# BSPD.net
KiCad netlist of a schematic drawn in Altium Designer
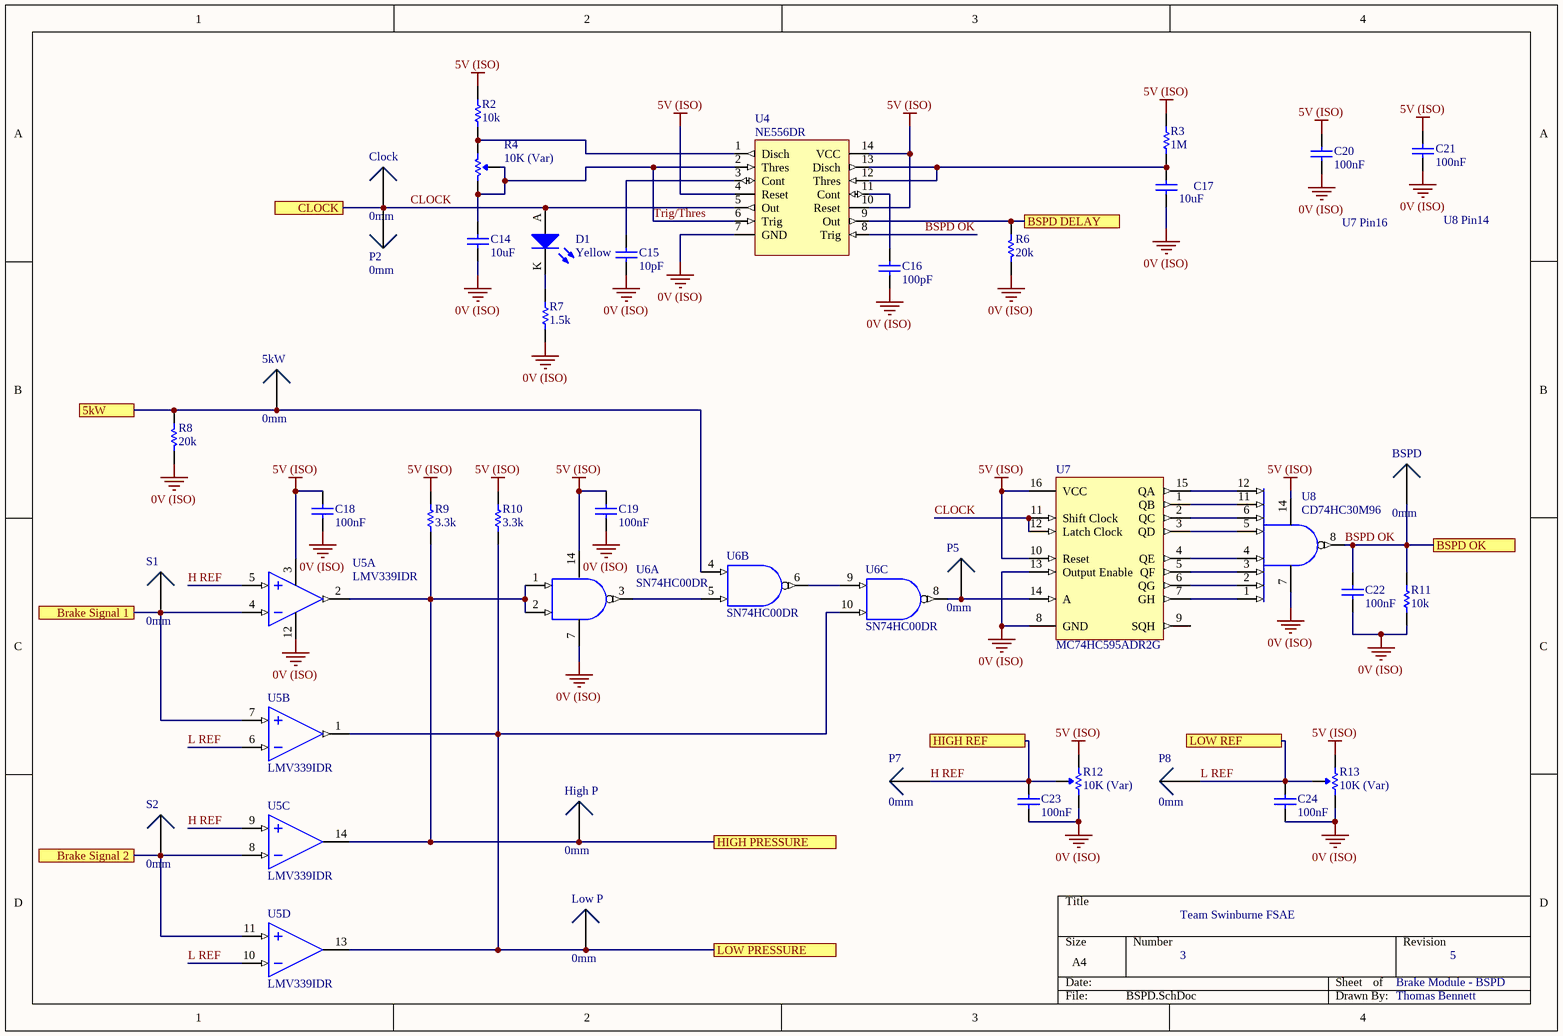
[diagram p0: BSPD.SchDoc]

(export (version "E")
  (design (tool "Eeschema 10.0.6"))
  (components
    (comp (ref "5kW")
      (value "0mm")
      (footprint "SMD Test Point")
      (fields (field (name "PART NUMBER") "SMD Test Point") (field (name "CONTACT") "NA"))
      (libsource (lib "ts_20-standard-connectors") (part "Test Point"))
    )
    (comp (ref "BSPD")
      (value "0mm")
      (footprint "SMD Test Point")
      (fields (field (name "PART NUMBER") "SMD Test Point") (field (name "CONTACT") "NA"))
      (libsource (lib "ts_20-standard-connectors") (part "Test Point"))
    )
    (comp (ref "C14")
      (value "10uF")
      (footprint "0805")
      (fields
        (field (name "PART NUMBER") "GRM21BR6YA106KE43L")
        (field (name "TOLERANCE") "10%")
        (field (name "MANUFACTURER") "muRata")
      )
      (libsource (lib "ts_20-standard-library") (part "Capacitor"))
    )
    (comp (ref "C15")
      (value "10pF")
      (footprint "0805")
      (fields
        (field (name "PART NUMBER") "GRM21A5C2E100JW01D")
        (field (name "TOLERANCE") "±5%")
        (field (name "MANUFACTURER") "muRata")
      )
      (libsource (lib "ts_20-standard-library") (part "Capacitor"))
    )
    (comp (ref "C16")
      (value "100pF")
      (footprint "0805")
      (fields
        (field (name "PART NUMBER") "GCM2165C1H101JA16D")
        (field (name "TOLERANCE") "±5%")
        (field (name "MANUFACTURER") "muRata")
      )
      (libsource (lib "ts_20-standard-library") (part "Capacitor"))
    )
    (comp (ref "C17")
      (value "10uF")
      (footprint "0805")
      (fields
        (field (name "PART NUMBER") "GRM21BR6YA106KE43L")
        (field (name "TOLERANCE") "10%")
        (field (name "MANUFACTURER") "muRata")
      )
      (libsource (lib "ts_20-standard-library") (part "Capacitor"))
    )
    (comp (ref "C18")
      (value "100nF")
      (footprint "0805")
      (fields
        (field (name "PART NUMBER") "GCM21BR71H104KA37L")
        (field (name "TOLERANCE") "±10%")
        (field (name "MANUFACTURER") "muRata")
      )
      (libsource (lib "ts_20-standard-library") (part "Capacitor"))
    )
    (comp (ref "C19")
      (value "100nF")
      (footprint "0805")
      (fields
        (field (name "PART NUMBER") "GCM21BR71E104KA37L")
        (field (name "TOLERANCE") "10%")
        (field (name "MANUFACTURER") "muRata")
      )
      (libsource (lib "ts_20-standard-library") (part "Capacitor"))
    )
    (comp (ref "C20")
      (value "100nF")
      (footprint "0805")
      (fields
        (field (name "PART NUMBER") "GCM21BR71H104KA37L")
        (field (name "TOLERANCE") "±10%")
        (field (name "MANUFACTURER") "muRata")
      )
      (libsource (lib "ts_20-standard-library") (part "Capacitor"))
    )
    (comp (ref "C21")
      (value "100nF")
      (footprint "0805")
      (fields
        (field (name "PART NUMBER") "GCM21BR71H104KA37L")
        (field (name "TOLERANCE") "±10%")
        (field (name "MANUFACTURER") "muRata")
      )
      (libsource (lib "ts_20-standard-library") (part "Capacitor"))
    )
    (comp (ref "C22")
      (value "100nF")
      (footprint "0805")
      (fields
        (field (name "PART NUMBER") "GCM21BR71H104KA37L")
        (field (name "TOLERANCE") "±10%")
        (field (name "MANUFACTURER") "muRata")
      )
      (libsource (lib "ts_20-standard-library") (part "Capacitor"))
    )
    (comp (ref "C23")
      (value "100nF")
      (footprint "0805")
      (fields
        (field (name "PART NUMBER") "GCM21BR71H104KA37L")
        (field (name "TOLERANCE") "±10%")
        (field (name "MANUFACTURER") "muRata")
      )
      (libsource (lib "ts_20-standard-library") (part "Capacitor"))
    )
    (comp (ref "C24")
      (value "100nF")
      (footprint "0805")
      (fields
        (field (name "PART NUMBER") "GCM21BR71H104KA37L")
        (field (name "TOLERANCE") "±10%")
        (field (name "MANUFACTURER") "muRata")
      )
      (libsource (lib "ts_20-standard-library") (part "Capacitor"))
    )
    (comp (ref "Clock")
      (value "0mm")
      (footprint "SMD Test Point")
      (fields (field (name "PART NUMBER") "SMD Test Point") (field (name "CONTACT") "NA"))
      (libsource (lib "ts_20-standard-connectors") (part "Test Point"))
    )
    (comp (ref "D1")
      (value "Yellow")
      (footprint "0805 LED")
      (description "Yellow LED Indication - Discrete 1.75V 0805 (2012 Metric)")
      (fields (field (name "PART NUMBER") "SML-211YTT86") (field (name "MANUFACTURER") "ROHM Semiconductor"))
      (libsource (lib "ts_20-standard-library") (part "LED"))
    )
    (comp (ref "High P")
      (value "0mm")
      (footprint "SMD Test Point")
      (fields (field (name "PART NUMBER") "SMD Test Point") (field (name "CONTACT") "NA"))
      (libsource (lib "ts_20-standard-connectors") (part "Test Point"))
    )
    (comp (ref "Low P")
      (value "0mm")
      (footprint "SMD Test Point")
      (fields (field (name "PART NUMBER") "SMD Test Point") (field (name "CONTACT") "NA"))
      (libsource (lib "ts_20-standard-connectors") (part "Test Point"))
    )
    (comp (ref "P2")
      (value "0mm")
      (footprint "TH Test Point")
      (fields (field (name "PART NUMBER") "TH Test Point") (field (name "CONTACT") "NA"))
      (libsource (lib "ts_20-standard-connectors") (part "Test Point"))
    )
    (comp (ref "P5")
      (value "0mm")
      (footprint "SMD Test Point")
      (fields (field (name "PART NUMBER") "SMD Test Point") (field (name "CONTACT") "NA"))
      (libsource (lib "ts_20-standard-connectors") (part "Test Point"))
    )
    (comp (ref "P7")
      (value "0mm")
      (footprint "TH Test Point")
      (fields (field (name "PART NUMBER") "TH Test Point") (field (name "CONTACT") "NA"))
      (libsource (lib "ts_20-standard-connectors") (part "Test Point"))
    )
    (comp (ref "P8")
      (value "0mm")
      (footprint "TH Test Point")
      (fields (field (name "PART NUMBER") "TH Test Point") (field (name "CONTACT") "NA"))
      (libsource (lib "ts_20-standard-connectors") (part "Test Point"))
    )
    (comp (ref "R2")
      (value "10k")
      (footprint "0805")
      (fields
        (field (name "PART NUMBER") "RC0805FR0710KL")
        (field (name "MANUFACTURER") "YAGEO")
        (field (name "TOLERANCE") "0.01")
      )
      (libsource (lib "ts_20-standard-library") (part "Resistor"))
    )
    (comp (ref "R3")
      (value "1M")
      (footprint "0805")
      (fields
        (field (name "PART NUMBER") "RC0805FR071ML")
        (field (name "MANUFACTURER") "YAGEO")
        (field (name "TOLERANCE") "0.01")
      )
      (libsource (lib "ts_20-standard-library") (part "Resistor"))
    )
    (comp (ref "R4")
      (value "10K (Var)")
      (footprint "B 3296")
      (fields
        (field (name "PART NUMBER") "3296W-1-103LF")
        (field (name "MANUFACTURER") "Bournes Inc")
        (field (name "TOLERANCE") "0.1")
      )
      (libsource (lib "ts_20-standard-library") (part "Resistor (Potentiometer)"))
    )
    (comp (ref "R6")
      (value "20k")
      (footprint "0805")
      (fields
        (field (name "PART NUMBER") "RC0805FR0720KL")
        (field (name "MANUFACTURER") "YAGEO")
        (field (name "TOLERANCE") "0.01")
      )
      (libsource (lib "ts_20-standard-library") (part "Resistor"))
    )
    (comp (ref "R7")
      (value "1.5k")
      (footprint "0805")
      (fields
        (field (name "PART NUMBER") "RC0805FR071K5L")
        (field (name "MANUFACTURER") "YAGEO")
        (field (name "TOLERANCE") "0.01")
      )
      (libsource (lib "ts_20-standard-library") (part "Resistor"))
    )
    (comp (ref "R8")
      (value "20k")
      (footprint "0805")
      (fields
        (field (name "PART NUMBER") "RC0805FR0720KL")
        (field (name "MANUFACTURER") "YAGEO")
        (field (name "TOLERANCE") "0.01")
      )
      (libsource (lib "ts_20-standard-library") (part "Resistor"))
    )
    (comp (ref "R9")
      (value "3.3k")
      (footprint "0805")
      (fields
        (field (name "PART NUMBER") "RC0805FR073K3L")
        (field (name "MANUFACTURER") "YAGEO")
        (field (name "TOLERANCE") "0.01")
      )
      (libsource (lib "ts_20-standard-library") (part "Resistor"))
    )
    (comp (ref "R10")
      (value "3.3k")
      (footprint "0805")
      (fields
        (field (name "PART NUMBER") "RC0805FR073K3L")
        (field (name "MANUFACTURER") "YAGEO")
        (field (name "TOLERANCE") "0.01")
      )
      (libsource (lib "ts_20-standard-library") (part "Resistor"))
    )
    (comp (ref "R11")
      (value "10k")
      (footprint "0805")
      (fields
        (field (name "PART NUMBER") "RC0805FR0710KL")
        (field (name "MANUFACTURER") "YAGEO")
        (field (name "TOLERANCE") "0.01")
      )
      (libsource (lib "ts_20-standard-library") (part "Resistor"))
    )
    (comp (ref "R12")
      (value "10K (Var)")
      (footprint "B 3296")
      (fields
        (field (name "PART NUMBER") "3296W-1-103LF")
        (field (name "MANUFACTURER") "Bournes Inc")
        (field (name "TOLERANCE") "0.1")
      )
      (libsource (lib "ts_20-standard-library") (part "Resistor (Potentiometer)"))
    )
    (comp (ref "R13")
      (value "10K (Var)")
      (footprint "B 3296")
      (fields
        (field (name "PART NUMBER") "3296W-1-103LF")
        (field (name "MANUFACTURER") "Bournes Inc")
        (field (name "TOLERANCE") "0.1")
      )
      (libsource (lib "ts_20-standard-library") (part "Resistor (Potentiometer)"))
    )
    (comp (ref "S1")
      (value "0mm")
      (footprint "TH Test Point")
      (fields (field (name "PART NUMBER") "TH Test Point") (field (name "CONTACT") "NA"))
      (libsource (lib "ts_20-standard-connectors") (part "Test Point"))
    )
    (comp (ref "S2")
      (value "0mm")
      (footprint "TH Test Point")
      (fields (field (name "PART NUMBER") "TH Test Point") (field (name "CONTACT") "NA"))
      (libsource (lib "ts_20-standard-connectors") (part "Test Point"))
    )
    (comp (ref "U4")
      (value "NE556DR")
      (footprint "14 SOIC")
      (description "IC OSC TIMER DUAL 100KHZ 14SOIC")
      (fields
        (field (name "MANUFACTURER") "Texas Instruments")
        (field (name "DIGIKEY PART NUMBER") "296-26240-1-ND")
      )
      (libsource (lib "ts_20-standard-library") (part "NE556DR"))
    )
    (comp (ref "U5")
      (value "LMV339IDR")
      (footprint "TI 14-SOIC")
      (description "Comparator General Purpose Open Collector 14-SOIC")
      (fields
        (field (name "MANUFACTURER") "Texas Instruments")
        (field (name "DIGIKEY PART NUMBER") "296-6611-2-ND")
      )
      (libsource (lib "ts_20-standard-library") (part "LMV339IDR"))
    )
    (comp (ref "U6")
      (value "SN74HC00DR")
      (footprint "TI 14-SOIC")
      (description "NAND Gate IC 4 Channel 14-SOIC")
      (fields
        (field (name "MANUFACTURER") "Texas Instruments")
        (field (name "DIGIKEY PART NUMBER") "296-1187-2-ND")
      )
      (libsource (lib "ts_20-standard-library") (part "SN74HC00DR"))
    )
    (comp (ref "U7")
      (value "MC74HC595ADR2G")
      (footprint "ON 16-SOIC")
      (description "IC SHIFT REGISTR 8BIT 3ST 16SOIC")
      (fields
        (field (name "MANUFACTURER") "ON Semiconductor")
        (field (name "DIGIKEY PART NUMBER") "MC74HC595ADR2GOSCT-ND")
      )
      (libsource (lib "ts_20-standard-library") (part "MC74HC595ADR2G"))
    )
    (comp (ref "U8")
      (value "CD74HC30M96")
      (footprint "TI 14-SOIC")
      (description "IC GATE NAND 1CH 8-INP 14SOIC")
      (fields
        (field (name "MANUFACTURER") "Texas Instruments")
        (field (name "DIGIKEY PART NUMBER") "296-14521-1-ND")
      )
      (libsource (lib "ts_20-standard-library") (part "CD74HC30M96"))
    )
  )
  (nets
    (net (code "1") (name "/5kW") (class "Default")
      (node (ref "5kW") (pin "1") (pinfunction "1_1") (pintype "passive"))
      (node (ref "R8") (pin "1") (pinfunction "1_1") (pintype "passive"))
      (node (ref "U6") (pin "4") (pinfunction "2A_4") (pintype "input"))
    )
    (net (code "2") (name "/BSPD DELAY") (class "Default")
      (node (ref "R6") (pin "1") (pinfunction "1_1") (pintype "passive"))
      (node (ref "U4") (pin "9") (pinfunction "Out_9") (pintype "output"))
    )
    (net (code "3") (name "/BSPD OK") (class "Default")
      (node (ref "BSPD") (pin "1") (pinfunction "1_1") (pintype "passive"))
      (node (ref "C22") (pin "2") (pinfunction "2_2") (pintype "passive"))
      (node (ref "R11") (pin "2") (pinfunction "2_2") (pintype "passive"))
      (node (ref "U4") (pin "8") (pinfunction "Trig_8") (pintype "input"))
      (node (ref "U8") (pin "8") (pinfunction "Output_8") (pintype "output"))
    )
    (net (code "4") (name "/Brake Signal 1") (class "Default")
      (node (ref "S1") (pin "1") (pinfunction "1_1") (pintype "passive"))
      (node (ref "U5") (pin "4") (pinfunction "IN_A-_4") (pintype "input"))
      (node (ref "U5") (pin "7") (pinfunction "IN_B+_7") (pintype "input"))
    )
    (net (code "5") (name "/Brake Signal 2") (class "Default")
      (node (ref "S2") (pin "1") (pinfunction "1_1") (pintype "passive"))
      (node (ref "U5") (pin "11") (pinfunction "IN_D+_11") (pintype "input"))
      (node (ref "U5") (pin "8") (pinfunction "IN_C-_8") (pintype "input"))
    )
    (net (code "6") (name "/CLOCK") (class "Default")
      (node (ref "Clock") (pin "1") (pinfunction "1_1") (pintype "passive"))
      (node (ref "D1") (pin "A") (pinfunction "A_A") (pintype "passive"))
      (node (ref "P2") (pin "1") (pinfunction "1_1") (pintype "passive"))
      (node (ref "U4") (pin "5") (pinfunction "Out_5") (pintype "output"))
      (node (ref "U7") (pin "11") (pinfunction "Shift_Clock_11") (pintype "input"))
      (node (ref "U7") (pin "12") (pinfunction "Latch_Clock_12") (pintype "input"))
    )
    (net (code "7") (name "/H REF") (class "Default")
      (node (ref "C23") (pin "2") (pinfunction "2_2") (pintype "passive"))
      (node (ref "P7") (pin "1") (pinfunction "1_1") (pintype "passive"))
      (node (ref "R12") (pin "2") (pinfunction "Wiper_2") (pintype "passive"))
      (node (ref "U5") (pin "5") (pinfunction "IN_A+_5") (pintype "input"))
      (node (ref "U5") (pin "9") (pinfunction "IN_C+_9") (pintype "input"))
    )
    (net (code "8") (name "/HIGH PRESSURE") (class "Default")
      (node (ref "High P") (pin "1") (pinfunction "1_1") (pintype "passive"))
      (node (ref "R9") (pin "1") (pinfunction "1_1") (pintype "passive"))
      (node (ref "U5") (pin "14") (pinfunction "OUT_C_14") (pintype "passive"))
      (node (ref "U5") (pin "2") (pinfunction "OUT_A_2") (pintype "output"))
      (node (ref "U6") (pin "1") (pinfunction "1A_1") (pintype "input"))
      (node (ref "U6") (pin "2") (pinfunction "1B_2") (pintype "input"))
    )
    (net (code "9") (name "/L REF") (class "Default")
      (node (ref "C24") (pin "2") (pinfunction "2_2") (pintype "passive"))
      (node (ref "P8") (pin "1") (pinfunction "1_1") (pintype "passive"))
      (node (ref "R13") (pin "2") (pinfunction "Wiper_2") (pintype "passive"))
      (node (ref "U5") (pin "10") (pinfunction "IN_D-_10") (pintype "input"))
      (node (ref "U5") (pin "6") (pinfunction "IN_B-_6") (pintype "input"))
    )
    (net (code "10") (name "/LOW PRESSURE") (class "Default")
      (node (ref "Low P") (pin "1") (pinfunction "1_1") (pintype "passive"))
      (node (ref "R10") (pin "1") (pinfunction "1_1") (pintype "passive"))
      (node (ref "U5") (pin "1") (pinfunction "OUT_B_1") (pintype "output"))
      (node (ref "U5") (pin "13") (pinfunction "OUT_D_13") (pintype "passive"))
      (node (ref "U6") (pin "10") (pinfunction "3B_10") (pintype "input"))
    )
    (net (code "11") (name "/Trig{slash}Thres") (class "Default")
      (node (ref "C14") (pin "2") (pinfunction "2_2") (pintype "passive"))
      (node (ref "R4") (pin "1") (pinfunction "CCW_1") (pintype "passive"))
      (node (ref "R4") (pin "2") (pinfunction "Wiper_2") (pintype "passive"))
      (node (ref "U4") (pin "2") (pinfunction "Thres_2") (pintype "input"))
      (node (ref "U4") (pin "6") (pinfunction "Trig_6") (pintype "input"))
    )
    (net (code "12") (name "0V (ISO)") (class "Default")
      (node (ref "C14") (pin "1") (pinfunction "1_1") (pintype "passive"))
      (node (ref "C15") (pin "1") (pinfunction "1_1") (pintype "passive"))
      (node (ref "C16") (pin "1") (pinfunction "1_1") (pintype "passive"))
      (node (ref "C17") (pin "1") (pinfunction "1_1") (pintype "passive"))
      (node (ref "C18") (pin "1") (pinfunction "1_1") (pintype "passive"))
      (node (ref "C19") (pin "1") (pinfunction "1_1") (pintype "passive"))
      (node (ref "C20") (pin "1") (pinfunction "1_1") (pintype "passive"))
      (node (ref "C21") (pin "1") (pinfunction "1_1") (pintype "passive"))
      (node (ref "C22") (pin "1") (pinfunction "1_1") (pintype "passive"))
      (node (ref "C23") (pin "1") (pinfunction "1_1") (pintype "passive"))
      (node (ref "C24") (pin "1") (pinfunction "1_1") (pintype "passive"))
      (node (ref "R11") (pin "1") (pinfunction "1_1") (pintype "passive"))
      (node (ref "R12") (pin "1") (pinfunction "CCW_1") (pintype "passive"))
      (node (ref "R13") (pin "1") (pinfunction "CCW_1") (pintype "passive"))
      (node (ref "R6") (pin "2") (pinfunction "2_2") (pintype "passive"))
      (node (ref "R7") (pin "1") (pinfunction "1_1") (pintype "passive"))
      (node (ref "R8") (pin "2") (pinfunction "2_2") (pintype "passive"))
      (node (ref "U4") (pin "7") (pinfunction "GND_7") (pintype "power_in"))
      (node (ref "U5") (pin "12") (pinfunction "V-_12") (pintype "power_in"))
      (node (ref "U6") (pin "7") (pinfunction "GND_7") (pintype "power_in"))
      (node (ref "U7") (pin "13") (pinfunction "Output_Enable_13") (pintype "input"))
      (node (ref "U7") (pin "8") (pinfunction "GND_8") (pintype "power_in"))
      (node (ref "U8") (pin "7") (pinfunction "GND_7") (pintype "power_in"))
    )
    (net (code "13") (name "5V (ISO)") (class "Default")
      (node (ref "C18") (pin "2") (pinfunction "2_2") (pintype "passive"))
      (node (ref "C19") (pin "2") (pinfunction "2_2") (pintype "passive"))
      (node (ref "C20") (pin "2") (pinfunction "2_2") (pintype "passive"))
      (node (ref "C21") (pin "2") (pinfunction "2_2") (pintype "passive"))
      (node (ref "R10") (pin "2") (pinfunction "2_2") (pintype "passive"))
      (node (ref "R12") (pin "3") (pinfunction "CW_3") (pintype "passive"))
      (node (ref "R13") (pin "3") (pinfunction "CW_3") (pintype "passive"))
      (node (ref "R2") (pin "2") (pinfunction "2_2") (pintype "passive"))
      (node (ref "R3") (pin "2") (pinfunction "2_2") (pintype "passive"))
      (node (ref "R9") (pin "2") (pinfunction "2_2") (pintype "passive"))
      (node (ref "U4") (pin "10") (pinfunction "Reset_10") (pintype "passive"))
      (node (ref "U4") (pin "14") (pinfunction "VCC_14") (pintype "passive"))
      (node (ref "U4") (pin "4") (pinfunction "Reset_4") (pintype "passive"))
      (node (ref "U5") (pin "3") (pinfunction "V+_3") (pintype "power_in"))
      (node (ref "U6") (pin "14") (pinfunction "VCC_14") (pintype "power_in"))
      (node (ref "U7") (pin "10") (pinfunction "Reset_10") (pintype "input"))
      (node (ref "U7") (pin "16") (pinfunction "VCC_16") (pintype "power_in"))
      (node (ref "U8") (pin "14") (pinfunction "VCC_14") (pintype "power_in"))
    )
    (net (code "14") (name "Net-(C15-Pad2)") (class "Default")
      (node (ref "C15") (pin "2") (pinfunction "2_2") (pintype "passive"))
      (node (ref "U4") (pin "3") (pinfunction "Cont_3") (pintype "bidirectional"))
    )
    (net (code "15") (name "Net-(C16-Pad2)") (class "Default")
      (node (ref "C16") (pin "2") (pinfunction "2_2") (pintype "passive"))
      (node (ref "U4") (pin "11") (pinfunction "Cont_11") (pintype "bidirectional"))
    )
    (net (code "16") (name "Net-(C17-Pad2)") (class "Default")
      (node (ref "C17") (pin "2") (pinfunction "2_2") (pintype "passive"))
      (node (ref "R3") (pin "1") (pinfunction "1_1") (pintype "passive"))
      (node (ref "U4") (pin "12") (pinfunction "Thres_12") (pintype "input"))
      (node (ref "U4") (pin "13") (pinfunction "Disch_13") (pintype "output"))
    )
    (net (code "17") (name "Net-(D1-PadK)") (class "Default")
      (node (ref "D1") (pin "K") (pinfunction "K_K") (pintype "passive"))
      (node (ref "R7") (pin "2") (pinfunction "2_2") (pintype "passive"))
    )
    (net (code "18") (name "Net-(R4-CW)") (class "Default")
      (node (ref "R2") (pin "1") (pinfunction "1_1") (pintype "passive"))
      (node (ref "R4") (pin "3") (pinfunction "CW_3") (pintype "passive"))
      (node (ref "U4") (pin "1") (pinfunction "Disch_1") (pintype "output"))
    )
    (net (code "19") (name "Net-(U6A-1Y)") (class "Default")
      (node (ref "U6") (pin "3") (pinfunction "1Y_3") (pintype "output"))
      (node (ref "U6") (pin "5") (pinfunction "2B_5") (pintype "input"))
    )
    (net (code "20") (name "Net-(U6B-2Y)") (class "Default")
      (node (ref "U6") (pin "6") (pinfunction "2Y_6") (pintype "output"))
      (node (ref "U6") (pin "9") (pinfunction "3A_9") (pintype "input"))
    )
    (net (code "21") (name "Net-(U6C-3Y)") (class "Default")
      (node (ref "P5") (pin "1") (pinfunction "1_1") (pintype "passive"))
      (node (ref "U6") (pin "8") (pinfunction "3Y_8") (pintype "output"))
      (node (ref "U7") (pin "14") (pinfunction "A_14") (pintype "input"))
    )
    (net (code "22") (name "Net-(U7-GH)") (class "Default")
      (node (ref "U7") (pin "7") (pinfunction "GH_7") (pintype "output"))
      (node (ref "U8") (pin "1") (pinfunction "Input_1") (pintype "input"))
    )
    (net (code "23") (name "Net-(U7-QA)") (class "Default")
      (node (ref "U7") (pin "15") (pinfunction "QA_15") (pintype "output"))
      (node (ref "U8") (pin "12") (pinfunction "Input_12") (pintype "input"))
    )
    (net (code "24") (name "Net-(U7-QB)") (class "Default")
      (node (ref "U7") (pin "1") (pinfunction "QB_1") (pintype "output"))
      (node (ref "U8") (pin "11") (pinfunction "Input_11") (pintype "input"))
    )
    (net (code "25") (name "Net-(U7-QC)") (class "Default")
      (node (ref "U7") (pin "2") (pinfunction "QC_2") (pintype "output"))
      (node (ref "U8") (pin "6") (pinfunction "Input_6") (pintype "input"))
    )
    (net (code "26") (name "Net-(U7-QD)") (class "Default")
      (node (ref "U7") (pin "3") (pinfunction "QD_3") (pintype "output"))
      (node (ref "U8") (pin "5") (pinfunction "Input_5") (pintype "input"))
    )
    (net (code "27") (name "Net-(U7-QE)") (class "Default")
      (node (ref "U7") (pin "4") (pinfunction "QE_4") (pintype "output"))
      (node (ref "U8") (pin "4") (pinfunction "Input_4") (pintype "input"))
    )
    (net (code "28") (name "Net-(U7-QF)") (class "Default")
      (node (ref "U7") (pin "5") (pinfunction "QF_5") (pintype "output"))
      (node (ref "U8") (pin "3") (pinfunction "Input_3") (pintype "input"))
    )
    (net (code "29") (name "Net-(U7-QG)") (class "Default")
      (node (ref "U7") (pin "6") (pinfunction "QG_6") (pintype "output"))
      (node (ref "U8") (pin "2") (pinfunction "Input_2") (pintype "input"))
    )
    (net (code "30") (name "unconnected-(U7-SQH-Pad9)") (class "Default")
      (node (ref "U7") (pin "9") (pinfunction "SQH_9") (pintype "output"))
    )
  )
)
